# openmv.net
KiCad netlist of a schematic drawn in EAGLE
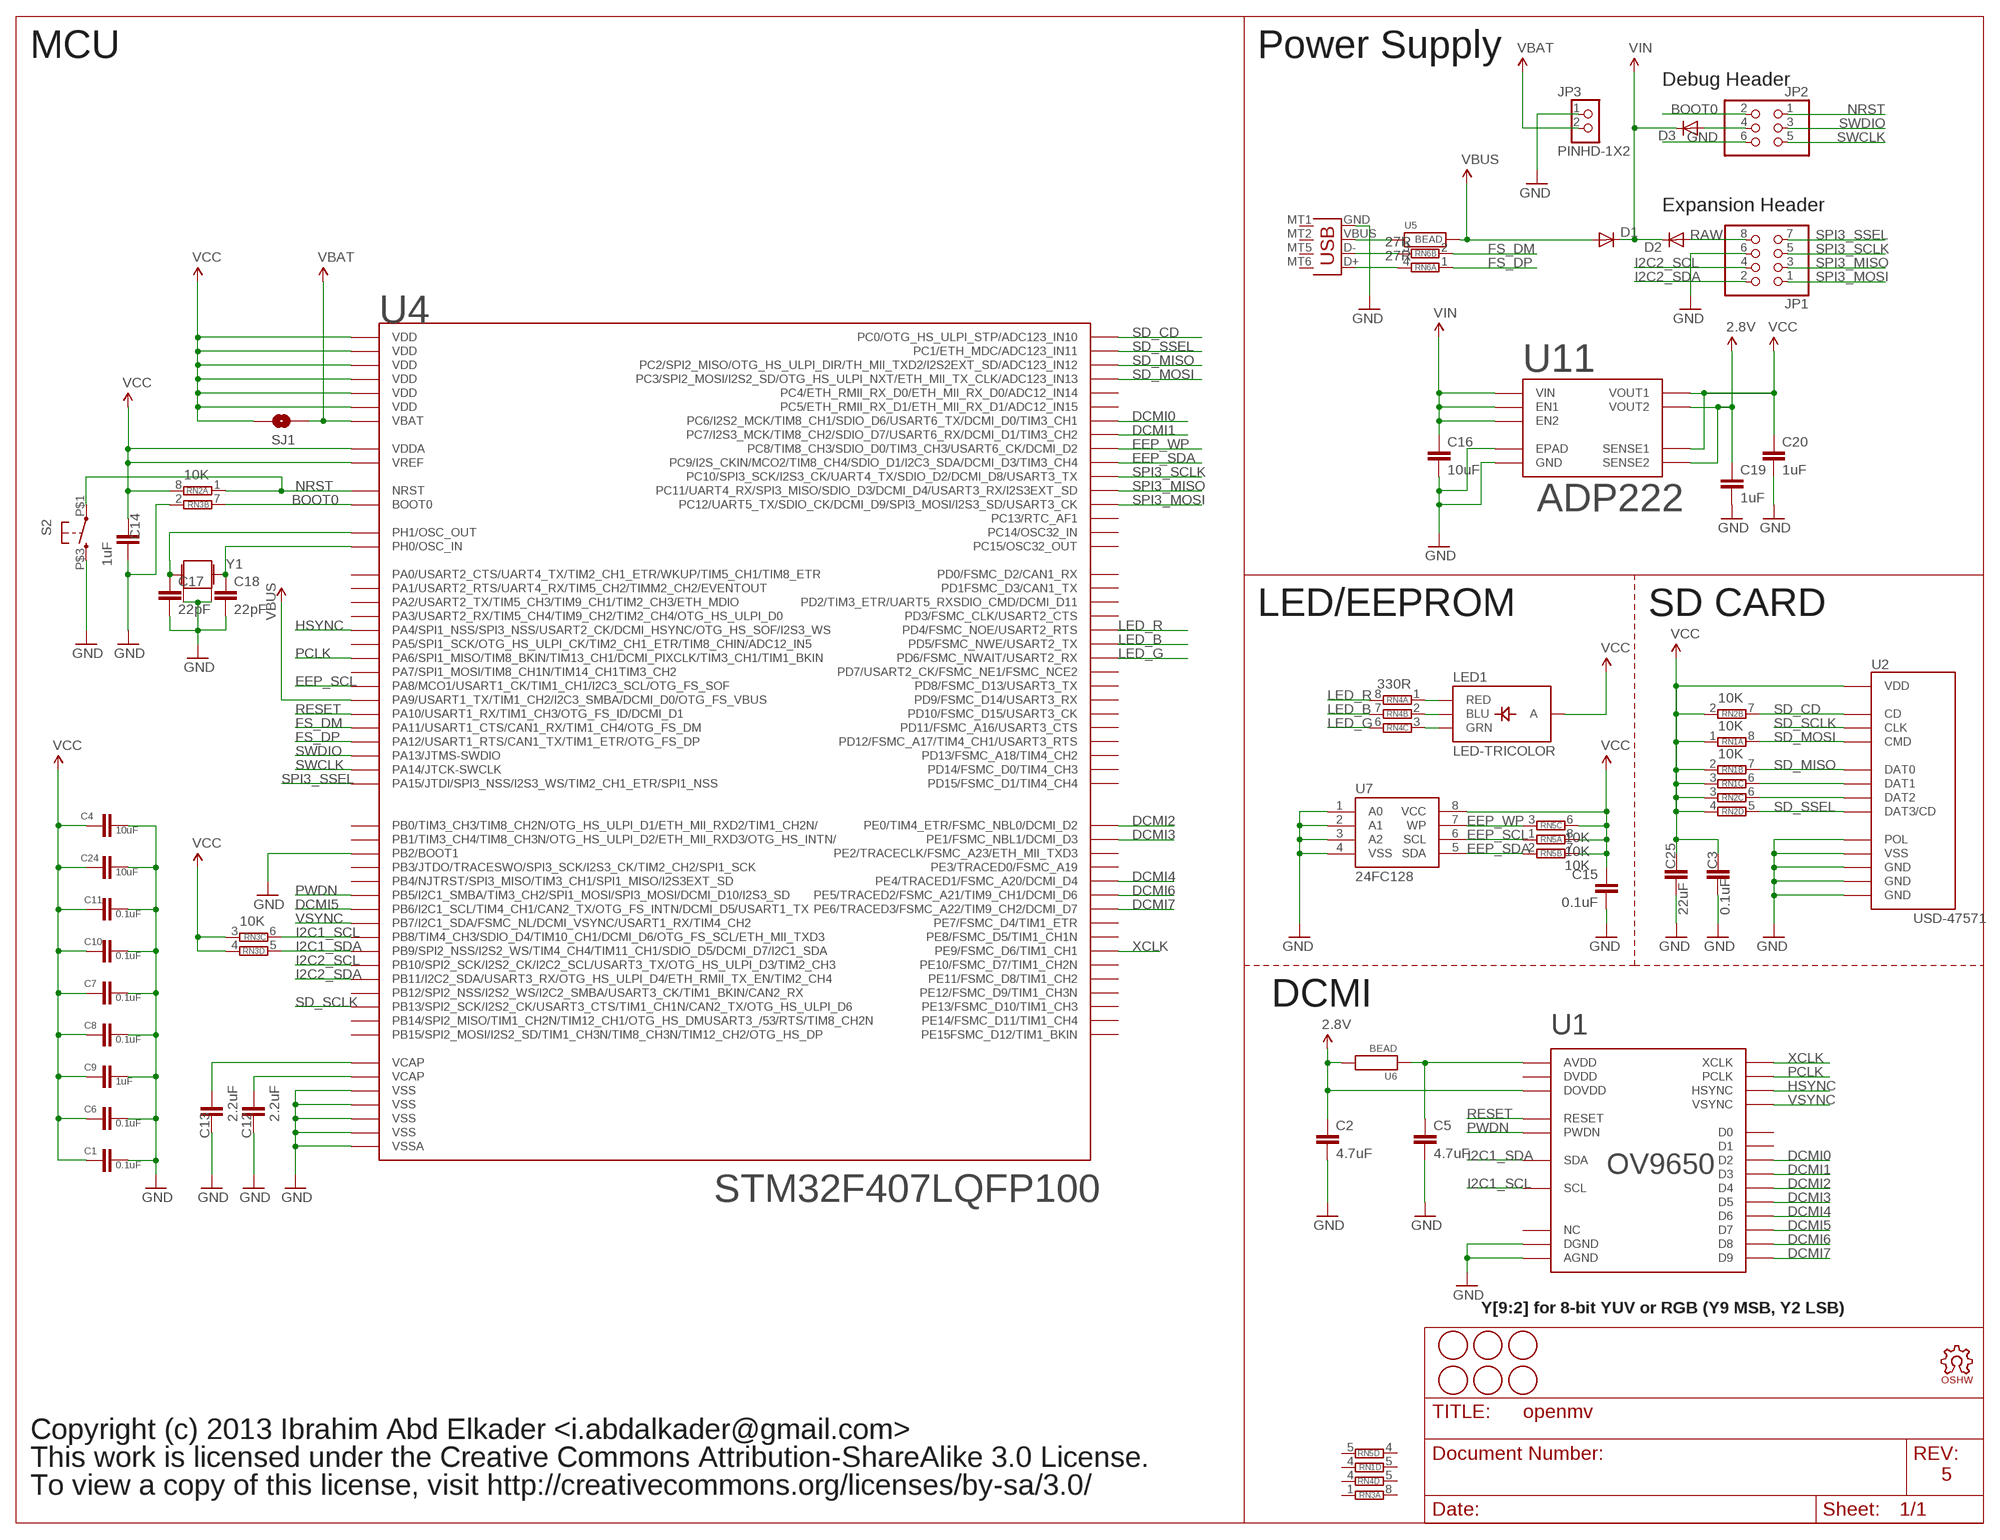
[diagram p0: schematic, sheet 1]

(export (version "E")
  (design (tool "Eeschema 10.0.6"))
  (components
    (comp (ref "C1")
      (value "0.1uF")
      (footprint "eagle-import:0402-CAP")
      (libsource (lib "eagle-import") (part "CAP0402-CAP"))
    )
    (comp (ref "C2")
      (value "4.7uF")
      (footprint "eagle-import:0402-CAP")
      (libsource (lib "eagle-import") (part "CAP0402-CAP"))
    )
    (comp (ref "C3")
      (value "0.1uF")
      (footprint "eagle-import:0402-CAP")
      (libsource (lib "eagle-import") (part "CAP0402-CAP"))
    )
    (comp (ref "C4")
      (value "10uF")
      (footprint "eagle-import:0805")
      (libsource (lib "eagle-import") (part "CAP0805"))
    )
    (comp (ref "C5")
      (value "4.7uF")
      (footprint "eagle-import:0402-CAP")
      (libsource (lib "eagle-import") (part "CAP0402-CAP"))
    )
    (comp (ref "C6")
      (value "0.1uF")
      (footprint "eagle-import:0402-CAP")
      (libsource (lib "eagle-import") (part "CAP0402-CAP"))
    )
    (comp (ref "C7")
      (value "0.1uF")
      (footprint "eagle-import:0402-CAP")
      (libsource (lib "eagle-import") (part "CAP0402-CAP"))
    )
    (comp (ref "C8")
      (value "0.1uF")
      (footprint "eagle-import:0402-CAP")
      (libsource (lib "eagle-import") (part "CAP0402-CAP"))
    )
    (comp (ref "C9")
      (value "1uF")
      (footprint "eagle-import:0402-CAP")
      (libsource (lib "eagle-import") (part "CAP0402-CAP"))
    )
    (comp (ref "C10")
      (value "0.1uF")
      (footprint "eagle-import:0402-CAP")
      (libsource (lib "eagle-import") (part "CAP0402-CAP"))
    )
    (comp (ref "C11")
      (value "0.1uF")
      (footprint "eagle-import:0402-CAP")
      (libsource (lib "eagle-import") (part "CAP0402-CAP"))
    )
    (comp (ref "C12")
      (value "2.2uF")
      (footprint "eagle-import:0402-CAP")
      (libsource (lib "eagle-import") (part "CAP0402-CAP"))
    )
    (comp (ref "C13")
      (value "2.2uF")
      (footprint "eagle-import:0402-CAP")
      (libsource (lib "eagle-import") (part "CAP0402-CAP"))
    )
    (comp (ref "C14")
      (value "1uF")
      (footprint "eagle-import:0402-CAP")
      (libsource (lib "eagle-import") (part "CAP0402-CAP"))
    )
    (comp (ref "C15")
      (value "0.1uF")
      (footprint "eagle-import:0402-CAP")
      (libsource (lib "eagle-import") (part "CAP0402-CAP"))
    )
    (comp (ref "C16")
      (value "10uF")
      (footprint "eagle-import:0805")
      (libsource (lib "eagle-import") (part "CAP0805"))
    )
    (comp (ref "C17")
      (value "22pF")
      (footprint "eagle-import:0402-CAP")
      (libsource (lib "eagle-import") (part "CAP0402-CAP"))
    )
    (comp (ref "C18")
      (value "22pF")
      (footprint "eagle-import:0402-CAP")
      (libsource (lib "eagle-import") (part "CAP0402-CAP"))
    )
    (comp (ref "C19")
      (value "1uF")
      (footprint "eagle-import:0402-CAP")
      (libsource (lib "eagle-import") (part "CAP0402-CAP"))
    )
    (comp (ref "C20")
      (value "1uF")
      (footprint "eagle-import:0402-CAP")
      (libsource (lib "eagle-import") (part "CAP0402-CAP"))
    )
    (comp (ref "C24")
      (value "10uF")
      (footprint "eagle-import:0805")
      (libsource (lib "eagle-import") (part "CAP0805"))
    )
    (comp (ref "C25")
      (value "22uF")
      (footprint "eagle-import:0805")
      (libsource (lib "eagle-import") (part "CAP0805"))
    )
    (comp (ref "D1")
      (value "DIODESOD")
      (footprint "eagle-import:SOD-323")
      (libsource (lib "eagle-import") (part "DIODESOD"))
    )
    (comp (ref "D2")
      (value "DIODESOD")
      (footprint "eagle-import:SOD-323")
      (libsource (lib "eagle-import") (part "DIODESOD"))
    )
    (comp (ref "D3")
      (value "DIODESOD")
      (footprint "eagle-import:SOD-323")
      (libsource (lib "eagle-import") (part "DIODESOD"))
    )
    (comp (ref "JP1")
      (value "PINHD-2X4")
      (footprint "eagle-import:2X04")
      (libsource (lib "eagle-import") (part "PINHD-2X4"))
    )
    (comp (ref "JP2")
      (value "PINHD-2X3")
      (footprint "eagle-import:2X03")
      (libsource (lib "eagle-import") (part "PINHD-2X3"))
    )
    (comp (ref "JP3")
      (value "PINHD-1X2")
      (footprint "eagle-import:1X2")
      (libsource (lib "eagle-import") (part "PINHD-1X2"))
    )
    (comp (ref "LED1")
      (value "LED-TRICOLOR")
      (footprint "eagle-import:LED-TRICOLOR-SMD")
      (libsource (lib "eagle-import") (part "LED-TRICOLOR"))
    )
    (comp (ref "LOGO1")
      (value "OSHW_LOGO_FILLX0150-NT")
      (footprint "eagle-import:OSHW_FILLX150_NOTEXT")
      (libsource (lib "eagle-import") (part "OSHW_LOGO_FILLX0150-NT"))
    )
    (comp (ref "RN1")
      (value "10K")
      (footprint "eagle-import:CAT16")
      (fields (field (name "OC_FARNELL") "unknown") (field (name "OC_NEWARK") "unknown"))
      (libsource (lib "eagle-import") (part "4R-NCAT16"))
    )
    (comp (ref "RN2")
      (value "10K")
      (footprint "eagle-import:CAT16")
      (fields (field (name "OC_FARNELL") "unknown") (field (name "OC_NEWARK") "unknown"))
      (libsource (lib "eagle-import") (part "4R-NCAT16"))
    )
    (comp (ref "RN3")
      (value "10K")
      (footprint "eagle-import:CAT16")
      (libsource (lib "eagle-import") (part "4R-NCAT16"))
    )
    (comp (ref "RN4")
      (value "330R")
      (footprint "eagle-import:CAT16")
      (fields (field (name "OC_FARNELL") "unknown") (field (name "OC_NEWARK") "unknown"))
      (libsource (lib "eagle-import") (part "4R-NCAT16"))
    )
    (comp (ref "RN5")
      (value "10K")
      (footprint "eagle-import:CAT16")
      (fields (field (name "OC_FARNELL") "unknown") (field (name "OC_NEWARK") "unknown"))
      (libsource (lib "eagle-import") (part "4R-NCAT16"))
    )
    (comp (ref "RN6")
      (value "27R")
      (footprint "eagle-import:EXBV4V")
      (libsource (lib "eagle-import") (part "2R-NEXBV4V"))
    )
    (comp (ref "S2")
      (value "SWITCHKMR442G")
      (footprint "eagle-import:KMR442G")
      (libsource (lib "eagle-import") (part "SWITCHKMR442G"))
    )
    (comp (ref "SJ1")
      (value "SOLDERJUMPERTRACE")
      (footprint "eagle-import:SJ_2S-TRACE")
      (libsource (lib "eagle-import") (part "SOLDERJUMPERTRACE"))
    )
    (comp (ref "U$3")
      (value "FIDUCIAL")
      (footprint "eagle-import:FIDUCIAL_1MM")
      (libsource (lib "eagle-import") (part "FIDUCIAL"))
    )
    (comp (ref "U$4")
      (value "FIDUCIAL")
      (footprint "eagle-import:FIDUCIAL_1MM")
      (libsource (lib "eagle-import") (part "FIDUCIAL"))
    )
    (comp (ref "U$5")
      (value "FIDUCIAL")
      (footprint "eagle-import:FIDUCIAL_1MM")
      (libsource (lib "eagle-import") (part "FIDUCIAL"))
    )
    (comp (ref "U$7")
      (value "FIDUCIAL")
      (footprint "eagle-import:FIDUCIAL_1MM")
      (libsource (lib "eagle-import") (part "FIDUCIAL"))
    )
    (comp (ref "U$9")
      (value "FIDUCIAL")
      (footprint "eagle-import:FIDUCIAL_1MM")
      (libsource (lib "eagle-import") (part "FIDUCIAL"))
    )
    (comp (ref "U$10")
      (value "FIDUCIAL")
      (footprint "eagle-import:FIDUCIAL_1MM")
      (libsource (lib "eagle-import") (part "FIDUCIAL"))
    )
    (comp (ref "U1")
      (value "OV9650")
      (footprint "eagle-import:OV9650")
      (libsource (lib "eagle-import") (part "OV9650"))
    )
    (comp (ref "U2")
      (value "USD-47571")
      (footprint "eagle-import:USD-47571")
      (libsource (lib "eagle-import") (part "USD-47571"))
    )
    (comp (ref "U4")
      (value "STM32F407LQFP100")
      (footprint "eagle-import:LQFP100")
      (libsource (lib "eagle-import") (part "STM32F407LQFP100"))
    )
    (comp (ref "U5")
      (value "BEAD")
      (footprint "eagle-import:0402-CAP")
      (libsource (lib "eagle-import") (part "BEAD"))
    )
    (comp (ref "U6")
      (value "BEAD")
      (footprint "eagle-import:0402-CAP")
      (libsource (lib "eagle-import") (part "BEAD"))
    )
    (comp (ref "U7")
      (value "24FC128")
      (footprint "eagle-import:MSOP8")
      (libsource (lib "eagle-import") (part "24FC128"))
    )
    (comp (ref "U11")
      (value "ADP222")
      (footprint "eagle-import:LFCSP8")
      (libsource (lib "eagle-import") (part "ADP222"))
    )
    (comp (ref "X1")
      (value "USB-MICROB")
      (footprint "eagle-import:USB-MICROB")
      (libsource (lib "eagle-import") (part "USB-MICROB"))
    )
    (comp (ref "Y1")
      (value "CRYSTAL2.5X2.0")
      (footprint "eagle-import:CRYSTAL-2.5X2.0")
      (libsource (lib "eagle-import") (part "CRYSTAL2.5X2.0"))
    )
  )
  (nets
    (net (code "1") (name "/BOOT0") (class "Default")
      (node (ref "JP2") (pin "2") (pinfunction "2_2") (pintype "passive"))
      (node (ref "RN3") (pin "7") (pinfunction "2_7") (pintype "passive"))
      (node (ref "U4") (pin "94") (pinfunction "BOOT0_94") (pintype "bidirectional"))
    )
    (net (code "2") (name "/DCMI0") (class "Default")
      (node (ref "U1") (pin "P$19") (pinfunction "D2_P$19") (pintype "bidirectional"))
      (node (ref "U4") (pin "63") (pinfunction "PC6/I2S2_MCK/TIM8_CH1/SDIO_D6/USART6_TX/DCMI_D0/TIM3_CH1_63") (pintype "bidirectional"))
    )
    (net (code "3") (name "/DCMI1") (class "Default")
      (node (ref "U1") (pin "P$21") (pinfunction "D3_P$21") (pintype "bidirectional"))
      (node (ref "U4") (pin "64") (pinfunction "PC7/I2S3_MCK/TIM8_CH2/SDIO_D7/USART6_RX/DCMI_D1/TIM3_CH2_64") (pintype "bidirectional"))
    )
    (net (code "4") (name "/DCMI2") (class "Default")
      (node (ref "U1") (pin "P$22") (pinfunction "D4_P$22") (pintype "bidirectional"))
      (node (ref "U4") (pin "97") (pinfunction "PE0/TIM4_ETR/FSMC_NBL0/DCMI_D2_97") (pintype "bidirectional"))
    )
    (net (code "5") (name "/DCMI3") (class "Default")
      (node (ref "U1") (pin "P$20") (pinfunction "D5_P$20") (pintype "bidirectional"))
      (node (ref "U4") (pin "98") (pinfunction "PE1/FSMC_NBL1/DCMI_D3_98") (pintype "bidirectional"))
    )
    (net (code "6") (name "/DCMI4") (class "Default")
      (node (ref "U1") (pin "P$18") (pinfunction "D6_P$18") (pintype "bidirectional"))
      (node (ref "U4") (pin "3") (pinfunction "PE4/TRACED1/FSMC_A20/DCMI_D4_3") (pintype "bidirectional"))
    )
    (net (code "7") (name "/DCMI5") (class "Default")
      (node (ref "U1") (pin "P$16") (pinfunction "D7_P$16") (pintype "bidirectional"))
      (node (ref "U4") (pin "92") (pinfunction "PB6/I2C1_SCL/TIM4_CH1/CAN2_TX/OTG_FS_INTN/DCMI_D5/USART1_TX_92") (pintype "bidirectional"))
    )
    (net (code "8") (name "/DCMI6") (class "Default")
      (node (ref "U1") (pin "P$14") (pinfunction "D8_P$14") (pintype "bidirectional"))
      (node (ref "U4") (pin "4") (pinfunction "PE5/TRACED2/FSMC_A21/TIM9_CH1/DCMI_D6_4") (pintype "bidirectional"))
    )
    (net (code "9") (name "/DCMI7") (class "Default")
      (node (ref "U1") (pin "P$12") (pinfunction "D9_P$12") (pintype "bidirectional"))
      (node (ref "U4") (pin "5") (pinfunction "PE6/TRACED3/FSMC_A22/TIM9_CH2/DCMI_D7_5") (pintype "bidirectional"))
    )
    (net (code "10") (name "/EEP_SCL") (class "Default")
      (node (ref "RN5") (pin "1") (pinfunction "1_1") (pintype "passive"))
      (node (ref "U4") (pin "67") (pinfunction "PA8/MCO1/USART1_CK/TIM1_CH1/I2C3_SCL/OTG_FS_SOF_67") (pintype "bidirectional"))
      (node (ref "U7") (pin "6") (pinfunction "SCL_6") (pintype "bidirectional"))
    )
    (net (code "11") (name "/EEP_SDA") (class "Default")
      (node (ref "RN5") (pin "2") (pinfunction "1_2") (pintype "passive"))
      (node (ref "U4") (pin "66") (pinfunction "PC9/I2S_CKIN/MCO2/TIM8_CH4/SDIO_D1/I2C3_SDA/DCMI_D3/TIM3_CH4_66") (pintype "bidirectional"))
      (node (ref "U7") (pin "5") (pinfunction "SDA_5") (pintype "bidirectional"))
    )
    (net (code "12") (name "/EEP_WP") (class "Default")
      (node (ref "RN5") (pin "3") (pinfunction "1_3") (pintype "passive"))
      (node (ref "U4") (pin "65") (pinfunction "PC8/TIM8_CH3/SDIO_D0/TIM3_CH3/USART6_CK/DCMI_D2_65") (pintype "bidirectional"))
      (node (ref "U7") (pin "7") (pinfunction "WP_7") (pintype "bidirectional"))
    )
    (net (code "13") (name "/FS_DM") (class "Default")
      (node (ref "RN6") (pin "2") (pinfunction "1_2") (pintype "passive"))
      (node (ref "U4") (pin "70") (pinfunction "PA11/USART1_CTS/CAN1_RX/TIM1_CH4/OTG_FS_DM_70") (pintype "bidirectional"))
    )
    (net (code "14") (name "/FS_DP") (class "Default")
      (node (ref "RN6") (pin "1") (pinfunction "1_1") (pintype "passive"))
      (node (ref "U4") (pin "71") (pinfunction "PA12/USART1_RTS/CAN1_TX/TIM1_ETR/OTG_FS_DP_71") (pintype "bidirectional"))
    )
    (net (code "15") (name "/HSYNC") (class "Default")
      (node (ref "U1") (pin "P$9") (pinfunction "HSYNC_P$9") (pintype "bidirectional"))
      (node (ref "U4") (pin "29") (pinfunction "PA4/SPI1_NSS/SPI3_NSS/USART2_CK/DCMI_HSYNC/OTG_HS_SOF/I2S3_WS_29") (pintype "bidirectional"))
    )
    (net (code "16") (name "/I2C1_SCL") (class "Default")
      (node (ref "RN3") (pin "6") (pinfunction "2_6") (pintype "passive"))
      (node (ref "U1") (pin "P$5") (pinfunction "SCL_P$5") (pintype "bidirectional"))
      (node (ref "U4") (pin "95") (pinfunction "PB8/TIM4_CH3/SDIO_D4/TIM10_CH1/DCMI_D6/OTG_FS_SCL/ETH_MII_TXD3_95") (pintype "bidirectional"))
    )
    (net (code "17") (name "/I2C1_SDA") (class "Default")
      (node (ref "RN3") (pin "5") (pinfunction "2_5") (pintype "passive"))
      (node (ref "U1") (pin "P$3") (pinfunction "SDA_P$3") (pintype "bidirectional"))
      (node (ref "U4") (pin "96") (pinfunction "PB9/SPI2_NSS/I2S2_WS/TIM4_CH4/TIM11_CH1/SDIO_D5/DCMI_D7/I2C1_SDA_96") (pintype "bidirectional"))
    )
    (net (code "18") (name "/I2C2_SCL") (class "Default")
      (node (ref "JP1") (pin "4") (pinfunction "4_4") (pintype "passive"))
      (node (ref "U4") (pin "47") (pinfunction "PB10/SPI2_SCK/I2S2_CK/I2C2_SCL/USART3_TX/OTG_HS_ULPI_D3/TIM2_CH3_47") (pintype "bidirectional"))
    )
    (net (code "19") (name "/I2C2_SDA") (class "Default")
      (node (ref "JP1") (pin "2") (pinfunction "2_2") (pintype "passive"))
      (node (ref "U4") (pin "48") (pinfunction "PB11/I2C2_SDA/USART3_RX/OTG_HS_ULPI_D4/ETH_RMII_TX_EN/TIM2_CH4_48") (pintype "bidirectional"))
    )
    (net (code "20") (name "/LED_B") (class "Default")
      (node (ref "RN4") (pin "7") (pinfunction "2_7") (pintype "passive"))
      (node (ref "U4") (pin "86") (pinfunction "PD5/FSMC_NWE/USART2_TX_86") (pintype "bidirectional"))
    )
    (net (code "21") (name "/LED_G") (class "Default")
      (node (ref "RN4") (pin "6") (pinfunction "2_6") (pintype "passive"))
      (node (ref "U4") (pin "87") (pinfunction "PD6/FSMC_NWAIT/USART2_RX_87") (pintype "bidirectional"))
    )
    (net (code "22") (name "/LED_R") (class "Default")
      (node (ref "RN4") (pin "8") (pinfunction "2_8") (pintype "passive"))
      (node (ref "U4") (pin "85") (pinfunction "PD4/FSMC_NOE/USART2_RTS_85") (pintype "bidirectional"))
    )
    (net (code "23") (name "/NRST") (class "Default")
      (node (ref "JP2") (pin "1") (pinfunction "1_1") (pintype "passive"))
      (node (ref "RN2") (pin "1") (pinfunction "1_1") (pintype "passive"))
      (node (ref "S2") (pin "P$1") (pinfunction "1_P$1") (pintype "passive"))
      (node (ref "U4") (pin "14") (pinfunction "NRST_14") (pintype "bidirectional"))
    )
    (net (code "24") (name "/PCLK") (class "Default")
      (node (ref "U1") (pin "P$17") (pinfunction "PCLK_P$17") (pintype "bidirectional"))
      (node (ref "U4") (pin "31") (pinfunction "PA6/SPI1_MISO/TIM8_BKIN/TIM13_CH1/DCMI_PIXCLK/TIM3_CH1/TIM1_BKIN_31") (pintype "bidirectional"))
    )
    (net (code "25") (name "/PWDN") (class "Default")
      (node (ref "U1") (pin "P$8") (pinfunction "PWDN_P$8") (pintype "bidirectional"))
      (node (ref "U4") (pin "91") (pinfunction "PB5/I2C1_SMBA/TIM3_CH2/SPI1_MOSI/SPI3_MOSI/DCMI_D10/I2S3_SD_91") (pintype "bidirectional"))
    )
    (net (code "26") (name "/RAW") (class "Default")
      (node (ref "D2") (pin "2") (pinfunction "A_2") (pintype "passive"))
      (node (ref "JP1") (pin "8") (pinfunction "8_8") (pintype "passive"))
    )
    (net (code "27") (name "/RESET") (class "Default")
      (node (ref "U1") (pin "P$6") (pinfunction "RESET_P$6") (pintype "bidirectional"))
      (node (ref "U4") (pin "69") (pinfunction "PA10/USART1_RX/TIM1_CH3/OTG_FS_ID/DCMI_D1_69") (pintype "bidirectional"))
    )
    (net (code "28") (name "/SD_CD") (class "Default")
      (node (ref "RN2") (pin "7") (pinfunction "2_7") (pintype "passive"))
      (node (ref "U2") (pin "G$5") (pinfunction "CD_G$5") (pintype "power_in"))
      (node (ref "U4") (pin "15") (pinfunction "PC0/OTG_HS_ULPI_STP/ADC123_IN10_15") (pintype "bidirectional"))
    )
    (net (code "29") (name "/SD_MISO") (class "Default")
      (node (ref "RN1") (pin "7") (pinfunction "2_7") (pintype "passive"))
      (node (ref "U2") (pin "P$7") (pinfunction "DAT0_P$7") (pintype "bidirectional"))
      (node (ref "U4") (pin "17") (pinfunction "PC2/SPI2_MISO/OTG_HS_ULPI_DIR/TH_MII_TXD2/I2S2EXT_SD/ADC123_IN12_17") (pintype "bidirectional"))
    )
    (net (code "30") (name "/SD_MOSI") (class "Default")
      (node (ref "RN1") (pin "8") (pinfunction "2_8") (pintype "passive"))
      (node (ref "U2") (pin "P$3") (pinfunction "CMD_P$3") (pintype "bidirectional"))
      (node (ref "U4") (pin "18") (pinfunction "PC3/SPI2_MOSI/I2S2_SD/OTG_HS_ULPI_NXT/ETH_MII_TX_CLK/ADC123_IN13_18") (pintype "bidirectional"))
    )
    (net (code "31") (name "/SD_SCLK") (class "Default")
      (node (ref "U2") (pin "P$5") (pinfunction "CLK_P$5") (pintype "bidirectional"))
      (node (ref "U4") (pin "52") (pinfunction "PB13/SPI2_SCK/I2S2_CK/USART3_CTS/TIM1_CH1N/CAN2_TX/OTG_HS_ULPI_D6_52") (pintype "bidirectional"))
    )
    (net (code "32") (name "/SD_SSEL") (class "Default")
      (node (ref "RN2") (pin "5") (pinfunction "2_5") (pintype "passive"))
      (node (ref "U2") (pin "P$2") (pinfunction "DAT3/CD_P$2") (pintype "bidirectional"))
      (node (ref "U4") (pin "16") (pinfunction "PC1/ETH_MDC/ADC123_IN11_16") (pintype "bidirectional"))
    )
    (net (code "33") (name "/SPI3_MISO") (class "Default")
      (node (ref "JP1") (pin "3") (pinfunction "3_3") (pintype "passive"))
      (node (ref "U4") (pin "79") (pinfunction "PC11/UART4_RX/SPI3_MISO/SDIO_D3/DCMI_D4/USART3_RX/I2S3EXT_SD_79") (pintype "bidirectional"))
    )
    (net (code "34") (name "/SPI3_MOSI") (class "Default")
      (node (ref "JP1") (pin "1") (pinfunction "1_1") (pintype "passive"))
      (node (ref "U4") (pin "80") (pinfunction "PC12/UART5_TX/SDIO_CK/DCMI_D9/SPI3_MOSI/I2S3_SD/USART3_CK_80") (pintype "bidirectional"))
    )
    (net (code "35") (name "/SPI3_SCLK") (class "Default")
      (node (ref "JP1") (pin "5") (pinfunction "5_5") (pintype "passive"))
      (node (ref "U4") (pin "78") (pinfunction "PC10/SPI3_SCK/I2S3_CK/UART4_TX/SDIO_D2/DCMI_D8/USART3_TX_78") (pintype "bidirectional"))
    )
    (net (code "36") (name "/SPI3_SSEL") (class "Default")
      (node (ref "JP1") (pin "7") (pinfunction "7_7") (pintype "passive"))
      (node (ref "U4") (pin "77") (pinfunction "PA15/JTDI/SPI3_NSS/I2S3_WS/TIM2_CH1_ETR/SPI1_NSS_77") (pintype "bidirectional"))
    )
    (net (code "37") (name "/SWCLK") (class "Default")
      (node (ref "JP2") (pin "5") (pinfunction "5_5") (pintype "passive"))
      (node (ref "U4") (pin "76") (pinfunction "PA14/JTCK-SWCLK_76") (pintype "bidirectional"))
    )
    (net (code "38") (name "/SWDIO") (class "Default")
      (node (ref "JP2") (pin "3") (pinfunction "3_3") (pintype "passive"))
      (node (ref "U4") (pin "72") (pinfunction "PA13/JTMS-SWDIO_72") (pintype "bidirectional"))
    )
    (net (code "39") (name "/VSYNC") (class "Default")
      (node (ref "U1") (pin "P$7") (pinfunction "VSYNC_P$7") (pintype "bidirectional"))
      (node (ref "U4") (pin "93") (pinfunction "PB7/I2C1_SDA/FSMC_NL/DCMI_VSYNC/USART1_RX/TIM4_CH2_93") (pintype "bidirectional"))
    )
    (net (code "40") (name "/XCLK") (class "Default")
      (node (ref "U1") (pin "P$13") (pinfunction "XCLK_P$13") (pintype "bidirectional"))
      (node (ref "U4") (pin "40") (pinfunction "PE9/FSMC_D6/TIM1_CH1_40") (pintype "bidirectional"))
    )
    (net (code "41") (name "2.8V") (class "Default")
      (node (ref "C19") (pin "1") (pinfunction "1_1") (pintype "passive"))
      (node (ref "C2") (pin "1") (pinfunction "1_1") (pintype "passive"))
      (node (ref "U1") (pin "P$11") (pinfunction "DOVDD_P$11") (pintype "bidirectional"))
      (node (ref "U11") (pin "4") (pinfunction "SENSE2_4") (pintype "passive"))
      (node (ref "U11") (pin "5") (pinfunction "VOUT2_5") (pintype "passive"))
      (node (ref "U6") (pin "2") (pinfunction "2_2") (pintype "passive"))
    )
    (net (code "42") (name "GND") (class "Default")
      (node (ref "C1") (pin "1") (pinfunction "1_1") (pintype "passive"))
      (node (ref "C10") (pin "2") (pinfunction "2_2") (pintype "passive"))
      (node (ref "C11") (pin "2") (pinfunction "2_2") (pintype "passive"))
      (node (ref "C12") (pin "2") (pinfunction "2_2") (pintype "passive"))
      (node (ref "C13") (pin "2") (pinfunction "2_2") (pintype "passive"))
      (node (ref "C14") (pin "1") (pinfunction "1_1") (pintype "passive"))
      (node (ref "C15") (pin "2") (pinfunction "2_2") (pintype "passive"))
      (node (ref "C16") (pin "2") (pinfunction "2_2") (pintype "passive"))
      (node (ref "C17") (pin "2") (pinfunction "2_2") (pintype "passive"))
      (node (ref "C18") (pin "2") (pinfunction "2_2") (pintype "passive"))
      (node (ref "C19") (pin "2") (pinfunction "2_2") (pintype "passive"))
      (node (ref "C2") (pin "2") (pinfunction "2_2") (pintype "passive"))
      (node (ref "C20") (pin "2") (pinfunction "2_2") (pintype "passive"))
      (node (ref "C24") (pin "1") (pinfunction "1_1") (pintype "passive"))
      (node (ref "C25") (pin "2") (pinfunction "2_2") (pintype "passive"))
      (node (ref "C3") (pin "2") (pinfunction "2_2") (pintype "passive"))
      (node (ref "C4") (pin "1") (pinfunction "1_1") (pintype "passive"))
      (node (ref "C5") (pin "2") (pinfunction "2_2") (pintype "passive"))
      (node (ref "C6") (pin "1") (pinfunction "1_1") (pintype "passive"))
      (node (ref "C7") (pin "2") (pinfunction "2_2") (pintype "passive"))
      (node (ref "C8") (pin "1") (pinfunction "1_1") (pintype "passive"))
      (node (ref "C9") (pin "1") (pinfunction "1_1") (pintype "passive"))
      (node (ref "JP1") (pin "6") (pinfunction "6_6") (pintype "passive"))
      (node (ref "JP2") (pin "6") (pinfunction "6_6") (pintype "passive"))
      (node (ref "JP3") (pin "1") (pinfunction "1_1") (pintype "passive"))
      (node (ref "RN3") (pin "2") (pinfunction "1_2") (pintype "passive"))
      (node (ref "S2") (pin "P$3") (pinfunction "2_P$3") (pintype "passive"))
      (node (ref "U1") (pin "P$15") (pinfunction "DGND_P$15") (pintype "bidirectional"))
      (node (ref "U1") (pin "P$2") (pinfunction "AGND_P$2") (pintype "power_in"))
      (node (ref "U11") (pin "3") (pinfunction "GND_3") (pintype "power_in"))
      (node (ref "U11") (pin "EXP") (pinfunction "EPAD_EXP") (pintype "input"))
      (node (ref "U2") (pin "G$1") (pinfunction "GND_G$1") (pintype "power_in"))
      (node (ref "U2") (pin "G$2") (pinfunction "GND_G$2") (pintype "power_in"))
      (node (ref "U2") (pin "G$3") (pinfunction "GND_G$3") (pintype "power_in"))
      (node (ref "U2") (pin "G$4") (pinfunction "POL_G$4") (pintype "power_in"))
      (node (ref "U2") (pin "P$6") (pinfunction "VSS_P$6") (pintype "power_in"))
      (node (ref "U4") (pin "10") (pinfunction "VSS_10") (pintype "power_in"))
      (node (ref "U4") (pin "20") (pinfunction "VSSA_20") (pintype "power_in"))
      (node (ref "U4") (pin "27") (pinfunction "VSS_27") (pintype "power_in"))
      (node (ref "U4") (pin "37") (pinfunction "PB2/BOOT1_37") (pintype "bidirectional"))
      (node (ref "U4") (pin "74") (pinfunction "VSS_74") (pintype "power_in"))
      (node (ref "U4") (pin "99") (pinfunction "VSS_99") (pintype "power_in"))
      (node (ref "U7") (pin "1") (pinfunction "A0_1") (pintype "bidirectional"))
      (node (ref "U7") (pin "2") (pinfunction "A1_2") (pintype "bidirectional"))
      (node (ref "U7") (pin "3") (pinfunction "A2_3") (pintype "bidirectional"))
      (node (ref "U7") (pin "4") (pinfunction "VSS_4") (pintype "power_in"))
      (node (ref "X1") (pin "GND") (pinfunction "GND_GND") (pintype "bidirectional"))
      (node (ref "Y1") (pin "2") (pinfunction "P$1_2") (pintype "power_in"))
      (node (ref "Y1") (pin "4") (pinfunction "P$2_4") (pintype "power_in"))
    )
    (net (code "43") (name "Net-(C12-Pad1)") (class "Default")
      (node (ref "C12") (pin "1") (pinfunction "1_1") (pintype "passive"))
      (node (ref "U4") (pin "73") (pinfunction "VCAP_73") (pintype "power_in"))
    )
    (net (code "44") (name "Net-(C13-Pad1)") (class "Default")
      (node (ref "C13") (pin "1") (pinfunction "1_1") (pintype "passive"))
      (node (ref "U4") (pin "49") (pinfunction "VCAP_49") (pintype "power_in"))
    )
    (net (code "45") (name "Net-(D3-A)") (class "Default")
      (node (ref "D3") (pin "2") (pinfunction "A_2") (pintype "passive"))
      (node (ref "JP2") (pin "4") (pinfunction "4_4") (pintype "passive"))
    )
    (net (code "46") (name "Net-(LED1-BLU)") (class "Default")
      (node (ref "LED1") (pin "B") (pinfunction "BLU_B") (pintype "bidirectional"))
      (node (ref "RN4") (pin "2") (pinfunction "1_2") (pintype "passive"))
    )
    (net (code "47") (name "Net-(LED1-GRN)") (class "Default")
      (node (ref "LED1") (pin "G") (pinfunction "GRN_G") (pintype "bidirectional"))
      (node (ref "RN4") (pin "3") (pinfunction "1_3") (pintype "passive"))
    )
    (net (code "48") (name "Net-(LED1-RED)") (class "Default")
      (node (ref "LED1") (pin "R") (pinfunction "RED_R") (pintype "bidirectional"))
      (node (ref "RN4") (pin "1") (pinfunction "1_1") (pintype "passive"))
    )
    (net (code "49") (name "Net-(RN1C-2)") (class "Default")
      (node (ref "RN1") (pin "6") (pinfunction "2_6") (pintype "passive"))
      (node (ref "U2") (pin "P$8") (pinfunction "DAT1_P$8") (pintype "bidirectional"))
    )
    (net (code "50") (name "Net-(RN2C-2)") (class "Default")
      (node (ref "RN2") (pin "6") (pinfunction "2_6") (pintype "passive"))
      (node (ref "U2") (pin "P$1") (pinfunction "DAT2_P$1") (pintype "bidirectional"))
    )
    (net (code "51") (name "Net-(RN6A-2)") (class "Default")
      (node (ref "RN6") (pin "4") (pinfunction "2_4") (pintype "passive"))
      (node (ref "X1") (pin "D+") (pinfunction "D+_D+") (pintype "bidirectional"))
    )
    (net (code "52") (name "Net-(RN6B-2)") (class "Default")
      (node (ref "RN6") (pin "3") (pinfunction "2_3") (pintype "passive"))
      (node (ref "X1") (pin "D-") (pinfunction "D-_D-") (pintype "bidirectional"))
    )
    (net (code "53") (name "Net-(U1-AVDD)") (class "Default")
      (node (ref "C5") (pin "1") (pinfunction "1_1") (pintype "passive"))
      (node (ref "U1") (pin "P$4") (pinfunction "AVDD_P$4") (pintype "power_in"))
      (node (ref "U6") (pin "1") (pinfunction "1_1") (pintype "passive"))
    )
    (net (code "54") (name "Net-(U4-PH0{slash}OSC_IN)") (class "Default")
      (node (ref "C18") (pin "1") (pinfunction "1_1") (pintype "passive"))
      (node (ref "U4") (pin "12") (pinfunction "PH0/OSC_IN_12") (pintype "bidirectional"))
      (node (ref "Y1") (pin "1") (pinfunction "1_1") (pintype "passive"))
    )
    (net (code "55") (name "Net-(U4-PH1{slash}OSC_OUT)") (class "Default")
      (node (ref "C17") (pin "1") (pinfunction "1_1") (pintype "passive"))
      (node (ref "U4") (pin "13") (pinfunction "PH1/OSC_OUT_13") (pintype "bidirectional"))
      (node (ref "Y1") (pin "3") (pinfunction "2_3") (pintype "passive"))
    )
    (net (code "56") (name "Net-(U5-Pad1)") (class "Default")
      (node (ref "U5") (pin "1") (pinfunction "1_1") (pintype "passive"))
      (node (ref "X1") (pin "VBUS") (pinfunction "VBUS_VBUS") (pintype "bidirectional"))
    )
    (net (code "57") (name "VBAT") (class "Default")
      (node (ref "JP3") (pin "2") (pinfunction "2_2") (pintype "passive"))
      (node (ref "SJ1") (pin "1") (pinfunction "1_1") (pintype "passive"))
      (node (ref "U4") (pin "6") (pinfunction "VBAT_6") (pintype "power_in"))
    )
    (net (code "58") (name "VBUS") (class "Default")
      (node (ref "D1") (pin "2") (pinfunction "A_2") (pintype "passive"))
      (node (ref "U4") (pin "68") (pinfunction "PA9/USART1_TX/TIM1_CH2/I2C3_SMBA/DCMI_D0/OTG_FS_VBUS_68") (pintype "bidirectional"))
      (node (ref "U5") (pin "2") (pinfunction "2_2") (pintype "passive"))
    )
    (net (code "59") (name "VCC") (class "Default")
      (node (ref "C1") (pin "2") (pinfunction "2_2") (pintype "passive"))
      (node (ref "C10") (pin "1") (pinfunction "1_1") (pintype "passive"))
      (node (ref "C11") (pin "1") (pinfunction "1_1") (pintype "passive"))
      (node (ref "C14") (pin "2") (pinfunction "2_2") (pintype "passive"))
      (node (ref "C15") (pin "1") (pinfunction "1_1") (pintype "passive"))
      (node (ref "C20") (pin "1") (pinfunction "1_1") (pintype "passive"))
      (node (ref "C24") (pin "2") (pinfunction "2_2") (pintype "passive"))
      (node (ref "C25") (pin "1") (pinfunction "1_1") (pintype "passive"))
      (node (ref "C3") (pin "1") (pinfunction "1_1") (pintype "passive"))
      (node (ref "C4") (pin "2") (pinfunction "2_2") (pintype "passive"))
      (node (ref "C6") (pin "2") (pinfunction "2_2") (pintype "passive"))
      (node (ref "C7") (pin "1") (pinfunction "1_1") (pintype "passive"))
      (node (ref "C8") (pin "2") (pinfunction "2_2") (pintype "passive"))
      (node (ref "C9") (pin "2") (pinfunction "2_2") (pintype "passive"))
      (node (ref "LED1") (pin "A") (pinfunction "A_A") (pintype "bidirectional"))
      (node (ref "RN1") (pin "1") (pinfunction "1_1") (pintype "passive"))
      (node (ref "RN1") (pin "2") (pinfunction "1_2") (pintype "passive"))
      (node (ref "RN1") (pin "3") (pinfunction "1_3") (pintype "passive"))
      (node (ref "RN2") (pin "2") (pinfunction "1_2") (pintype "passive"))
      (node (ref "RN2") (pin "3") (pinfunction "1_3") (pintype "passive"))
      (node (ref "RN2") (pin "4") (pinfunction "1_4") (pintype "passive"))
      (node (ref "RN2") (pin "8") (pinfunction "2_8") (pintype "passive"))
      (node (ref "RN3") (pin "3") (pinfunction "1_3") (pintype "passive"))
      (node (ref "RN3") (pin "4") (pinfunction "1_4") (pintype "passive"))
      (node (ref "RN5") (pin "6") (pinfunction "2_6") (pintype "passive"))
      (node (ref "RN5") (pin "7") (pinfunction "2_7") (pintype "passive"))
      (node (ref "RN5") (pin "8") (pinfunction "2_8") (pintype "passive"))
      (node (ref "SJ1") (pin "2") (pinfunction "2_2") (pintype "passive"))
      (node (ref "U11") (pin "7") (pinfunction "VOUT1_7") (pintype "passive"))
      (node (ref "U11") (pin "8") (pinfunction "SENSE1_8") (pintype "passive"))
      (node (ref "U2") (pin "P$4") (pinfunction "VDD_P$4") (pintype "power_in"))
      (node (ref "U4") (pin "100") (pinfunction "VDD_100") (pintype "power_in"))
      (node (ref "U4") (pin "11") (pinfunction "VDD_11") (pintype "power_in"))
      (node (ref "U4") (pin "19") (pinfunction "VDD_19") (pintype "power_in"))
      (node (ref "U4") (pin "21") (pinfunction "VREF_21") (pintype "power_in"))
      (node (ref "U4") (pin "22") (pinfunction "VDDA_22") (pintype "power_in"))
      (node (ref "U4") (pin "28") (pinfunction "VDD_28") (pintype "power_in"))
      (node (ref "U4") (pin "50") (pinfunction "VDD_50") (pintype "power_in"))
      (node (ref "U4") (pin "75") (pinfunction "VDD_75") (pintype "power_in"))
      (node (ref "U7") (pin "8") (pinfunction "VCC_8") (pintype "power_in"))
    )
    (net (code "60") (name "VIN") (class "Default")
      (node (ref "C16") (pin "1") (pinfunction "1_1") (pintype "passive"))
      (node (ref "D1") (pin "1") (pinfunction "C_1") (pintype "passive"))
      (node (ref "D2") (pin "1") (pinfunction "C_1") (pintype "passive"))
      (node (ref "D3") (pin "1") (pinfunction "C_1") (pintype "passive"))
      (node (ref "U11") (pin "1") (pinfunction "EN1_1") (pintype "input"))
      (node (ref "U11") (pin "2") (pinfunction "EN2_2") (pintype "input"))
      (node (ref "U11") (pin "6") (pinfunction "VIN_6") (pintype "power_in"))
    )
    (net (code "61") (name "unconnected-(RN1D-1-Pad4)") (class "Default")
      (node (ref "RN1") (pin "4") (pinfunction "1_4") (pintype "passive"))
    )
    (net (code "62") (name "unconnected-(RN1D-2-Pad5)") (class "Default")
      (node (ref "RN1") (pin "5") (pinfunction "2_5") (pintype "passive"))
    )
    (net (code "63") (name "unconnected-(RN3-Pad1)") (class "Default")
      (node (ref "RN3") (pin "1") (pinfunction "1_1") (pintype "passive"))
    )
    (net (code "64") (name "unconnected-(RN3A-2-Pad8)") (class "Default")
      (node (ref "RN3") (pin "8") (pinfunction "2_8") (pintype "passive"))
    )
    (net (code "65") (name "unconnected-(RN4D-1-Pad4)") (class "Default")
      (node (ref "RN4") (pin "4") (pinfunction "1_4") (pintype "passive"))
    )
    (net (code "66") (name "unconnected-(RN4D-2-Pad5)") (class "Default")
      (node (ref "RN4") (pin "5") (pinfunction "2_5") (pintype "passive"))
    )
    (net (code "67") (name "unconnected-(RN5D-1-Pad4)") (class "Default")
      (node (ref "RN5") (pin "4") (pinfunction "1_4") (pintype "passive"))
    )
    (net (code "68") (name "unconnected-(RN5D-2-Pad5)") (class "Default")
      (node (ref "RN5") (pin "5") (pinfunction "2_5") (pintype "passive"))
    )
    (net (code "69") (name "unconnected-(U1-D0-PadP$24)") (class "Default")
      (node (ref "U1") (pin "P$24") (pinfunction "D0_P$24") (pintype "bidirectional"))
    )
    (net (code "70") (name "unconnected-(U1-D1-PadP$23)") (class "Default")
      (node (ref "U1") (pin "P$23") (pinfunction "D1_P$23") (pintype "bidirectional"))
    )
    (net (code "71") (name "unconnected-(U1-DVDD-PadP$10)") (class "Default")
      (node (ref "U1") (pin "P$10") (pinfunction "DVDD_P$10") (pintype "bidirectional"))
    )
    (net (code "72") (name "unconnected-(U1-NC-PadP$1)") (class "Default")
      (node (ref "U1") (pin "P$1") (pinfunction "NC_P$1") (pintype "no_connect"))
    )
    (net (code "73") (name "unconnected-(U4-PA0{slash}USART2_CTS{slash}UART4_TX{slash}TIM2_CH1_ETR{slash}WKUP{slash}TIM5_CH1{slash}TIM8_ETR-Pad23)") (class "Default")
      (node (ref "U4") (pin "23") (pinfunction "PA0/USART2_CTS/UART4_TX/TIM2_CH1_ETR/WKUP/TIM5_CH1/TIM8_ETR_23") (pintype "bidirectional"))
    )
    (net (code "74") (name "unconnected-(U4-PA1{slash}USART2_RTS{slash}UART4_RX{slash}TIM5_CH2{slash}TIMM2_CH2{slash}EVENTOUT-Pad24)") (class "Default")
      (node (ref "U4") (pin "24") (pinfunction "PA1/USART2_RTS/UART4_RX/TIM5_CH2/TIMM2_CH2/EVENTOUT_24") (pintype "bidirectional"))
    )
    (net (code "75") (name "unconnected-(U4-PA2{slash}USART2_TX{slash}TIM5_CH3{slash}TIM9_CH1{slash}TIM2_CH3{slash}ETH_MDIO-Pad25)") (class "Default")
      (node (ref "U4") (pin "25") (pinfunction "PA2/USART2_TX/TIM5_CH3/TIM9_CH1/TIM2_CH3/ETH_MDIO_25") (pintype "bidirectional"))
    )
    (net (code "76") (name "unconnected-(U4-PA3{slash}USART2_RX{slash}TIM5_CH4{slash}TIM9_CH2{slash}TIM2_CH4{slash}OTG_HS_ULPI_D0-Pad26)") (class "Default")
      (node (ref "U4") (pin "26") (pinfunction "PA3/USART2_RX/TIM5_CH4/TIM9_CH2/TIM2_CH4/OTG_HS_ULPI_D0_26") (pintype "bidirectional"))
    )
    (net (code "77") (name "unconnected-(U4-PA5{slash}SPI1_SCK{slash}OTG_HS_ULPI_CK{slash}TIM2_CH1_ETR{slash}TIM8_CHIN{slash}ADC12_IN5-Pad30)") (class "Default")
      (node (ref "U4") (pin "30") (pinfunction "PA5/SPI1_SCK/OTG_HS_ULPI_CK/TIM2_CH1_ETR/TIM8_CHIN/ADC12_IN5_30") (pintype "bidirectional"))
    )
    (net (code "78") (name "unconnected-(U4-PA7{slash}SPI1_MOSI{slash}TIM8_CH1N{slash}TIM14_CH1TIM3_CH2-Pad32)") (class "Default")
      (node (ref "U4") (pin "32") (pinfunction "PA7/SPI1_MOSI/TIM8_CH1N/TIM14_CH1TIM3_CH2_32") (pintype "bidirectional"))
    )
    (net (code "79") (name "unconnected-(U4-PB0{slash}TIM3_CH3{slash}TIM8_CH2N{slash}OTG_HS_ULPI_D1{slash}ETH_MII_RXD2{slash}TIM1_CH2N{slash}-Pad35)") (class "Default")
      (node (ref "U4") (pin "35") (pinfunction "PB0/TIM3_CH3/TIM8_CH2N/OTG_HS_ULPI_D1/ETH_MII_RXD2/TIM1_CH2N/_35") (pintype "bidirectional"))
    )
    (net (code "80") (name "unconnected-(U4-PB1{slash}TIM3_CH4{slash}TIM8_CH3N{slash}OTG_HS_ULPI_D2{slash}ETH_MII_RXD3{slash}OTG_HS_INTN{slash}-Pad36)") (class "Default")
      (node (ref "U4") (pin "36") (pinfunction "PB1/TIM3_CH4/TIM8_CH3N/OTG_HS_ULPI_D2/ETH_MII_RXD3/OTG_HS_INTN/_36") (pintype "bidirectional"))
    )
    (net (code "81") (name "unconnected-(U4-PB3{slash}JTDO{slash}TRACESWO{slash}SPI3_SCK{slash}I2S3_CK{slash}TIM2_CH2{slash}SPI1_SCK-Pad89)") (class "Default")
      (node (ref "U4") (pin "89") (pinfunction "PB3/JTDO/TRACESWO/SPI3_SCK/I2S3_CK/TIM2_CH2/SPI1_SCK_89") (pintype "bidirectional"))
    )
    (net (code "82") (name "unconnected-(U4-PB4{slash}NJTRST{slash}SPI3_MISO{slash}TIM3_CH1{slash}SPI1_MISO{slash}I2S3EXT_SD-Pad90)") (class "Default")
      (node (ref "U4") (pin "90") (pinfunction "PB4/NJTRST/SPI3_MISO/TIM3_CH1/SPI1_MISO/I2S3EXT_SD_90") (pintype "bidirectional"))
    )
    (net (code "83") (name "unconnected-(U4-PB12{slash}SPI2_NSS{slash}I2S2_WS{slash}I2C2_SMBA{slash}USART3_CK{slash}TIM1_BKIN{slash}CAN2_RX-Pad51)") (class "Default")
      (node (ref "U4") (pin "51") (pinfunction "PB12/SPI2_NSS/I2S2_WS/I2C2_SMBA/USART3_CK/TIM1_BKIN/CAN2_RX_51") (pintype "bidirectional"))
    )
    (net (code "84") (name "unconnected-(U4-PB14{slash}SPI2_MISO{slash}TIM1_CH2N{slash}TIM12_CH1{slash}OTG_HS_DMUSART3_{slash}53{slash}RTS{slash}TIM8_CH2N-Pad53)") (class "Default")
      (node (ref "U4") (pin "53") (pinfunction "PB14/SPI2_MISO/TIM1_CH2N/TIM12_CH1/OTG_HS_DMUSART3_/53/RTS/TIM8_CH2N_53") (pintype "bidirectional"))
    )
    (net (code "85") (name "unconnected-(U4-PB15{slash}SPI2_MOSI{slash}I2S2_SD{slash}TIM1_CH3N{slash}TIM8_CH3N{slash}TIM12_CH2{slash}OTG_HS_DP-Pad54)") (class "Default")
      (node (ref "U4") (pin "54") (pinfunction "PB15/SPI2_MOSI/I2S2_SD/TIM1_CH3N/TIM8_CH3N/TIM12_CH2/OTG_HS_DP_54") (pintype "bidirectional"))
    )
    (net (code "86") (name "unconnected-(U4-PC4{slash}ETH_RMII_RX_D0{slash}ETH_MII_RX_D0{slash}ADC12_IN14-Pad33)") (class "Default")
      (node (ref "U4") (pin "33") (pinfunction "PC4/ETH_RMII_RX_D0/ETH_MII_RX_D0/ADC12_IN14_33") (pintype "bidirectional"))
    )
    (net (code "87") (name "unconnected-(U4-PC5{slash}ETH_RMII_RX_D1{slash}ETH_MII_RX_D1{slash}ADC12_IN15-Pad34)") (class "Default")
      (node (ref "U4") (pin "34") (pinfunction "PC5/ETH_RMII_RX_D1/ETH_MII_RX_D1/ADC12_IN15_34") (pintype "bidirectional"))
    )
    (net (code "88") (name "unconnected-(U4-PC13{slash}RTC_AF1-Pad7)") (class "Default")
      (node (ref "U4") (pin "7") (pinfunction "PC13/RTC_AF1_7") (pintype "bidirectional"))
    )
    (net (code "89") (name "unconnected-(U4-PC14{slash}OSC32_IN-Pad8)") (class "Default")
      (node (ref "U4") (pin "8") (pinfunction "PC14/OSC32_IN_8") (pintype "bidirectional"))
    )
    (net (code "90") (name "unconnected-(U4-PC15{slash}OSC32_OUT-Pad9)") (class "Default")
      (node (ref "U4") (pin "9") (pinfunction "PC15/OSC32_OUT_9") (pintype "bidirectional"))
    )
    (net (code "91") (name "unconnected-(U4-PD0{slash}FSMC_D2{slash}CAN1_RX-Pad81)") (class "Default")
      (node (ref "U4") (pin "81") (pinfunction "PD0/FSMC_D2/CAN1_RX_81") (pintype "bidirectional"))
    )
    (net (code "92") (name "unconnected-(U4-PD1FSMC_D3{slash}CAN1_TX-Pad82)") (class "Default")
      (node (ref "U4") (pin "82") (pinfunction "PD1FSMC_D3/CAN1_TX_82") (pintype "bidirectional"))
    )
    (net (code "93") (name "unconnected-(U4-PD2{slash}TIM3_ETR{slash}UART5_RXSDIO_CMD{slash}DCMI_D11-Pad83)") (class "Default")
      (node (ref "U4") (pin "83") (pinfunction "PD2/TIM3_ETR/UART5_RXSDIO_CMD/DCMI_D11_83") (pintype "bidirectional"))
    )
    (net (code "94") (name "unconnected-(U4-PD3{slash}FSMC_CLK{slash}USART2_CTS-Pad84)") (class "Default")
      (node (ref "U4") (pin "84") (pinfunction "PD3/FSMC_CLK/USART2_CTS_84") (pintype "bidirectional"))
    )
    (net (code "95") (name "unconnected-(U4-PD7{slash}USART2_CK{slash}FSMC_NE1{slash}FSMC_NCE2-Pad88)") (class "Default")
      (node (ref "U4") (pin "88") (pinfunction "PD7/USART2_CK/FSMC_NE1/FSMC_NCE2_88") (pintype "bidirectional"))
    )
    (net (code "96") (name "unconnected-(U4-PD8{slash}FSMC_D13{slash}USART3_TX-Pad55)") (class "Default")
      (node (ref "U4") (pin "55") (pinfunction "PD8/FSMC_D13/USART3_TX_55") (pintype "bidirectional"))
    )
    (net (code "97") (name "unconnected-(U4-PD9{slash}FSMC_D14{slash}USART3_RX-Pad56)") (class "Default")
      (node (ref "U4") (pin "56") (pinfunction "PD9/FSMC_D14/USART3_RX_56") (pintype "bidirectional"))
    )
    (net (code "98") (name "unconnected-(U4-PD10{slash}FSMC_D15{slash}USART3_CK-Pad57)") (class "Default")
      (node (ref "U4") (pin "57") (pinfunction "PD10/FSMC_D15/USART3_CK_57") (pintype "bidirectional"))
    )
    (net (code "99") (name "unconnected-(U4-PD11{slash}FSMC_A16{slash}USART3_CTS-Pad58)") (class "Default")
      (node (ref "U4") (pin "58") (pinfunction "PD11/FSMC_A16/USART3_CTS_58") (pintype "bidirectional"))
    )
    (net (code "100") (name "unconnected-(U4-PD12{slash}FSMC_A17{slash}TIM4_CH1{slash}USART3_RTS-Pad59)") (class "Default")
      (node (ref "U4") (pin "59") (pinfunction "PD12/FSMC_A17/TIM4_CH1/USART3_RTS_59") (pintype "bidirectional"))
    )
    (net (code "101") (name "unconnected-(U4-PD13{slash}FSMC_A18{slash}TIM4_CH2-Pad60)") (class "Default")
      (node (ref "U4") (pin "60") (pinfunction "PD13/FSMC_A18/TIM4_CH2_60") (pintype "bidirectional"))
    )
    (net (code "102") (name "unconnected-(U4-PD14{slash}FSMC_D0{slash}TIM4_CH3-Pad61)") (class "Default")
      (node (ref "U4") (pin "61") (pinfunction "PD14/FSMC_D0/TIM4_CH3_61") (pintype "bidirectional"))
    )
    (net (code "103") (name "unconnected-(U4-PD15{slash}FSMC_D1{slash}TIM4_CH4-Pad62)") (class "Default")
      (node (ref "U4") (pin "62") (pinfunction "PD15/FSMC_D1/TIM4_CH4_62") (pintype "bidirectional"))
    )
    (net (code "104") (name "unconnected-(U4-PE2{slash}TRACECLK{slash}FSMC_A23{slash}ETH_MII_TXD3-Pad1)") (class "Default")
      (node (ref "U4") (pin "1") (pinfunction "PE2/TRACECLK/FSMC_A23/ETH_MII_TXD3_1") (pintype "bidirectional"))
    )
    (net (code "105") (name "unconnected-(U4-PE3{slash}TRACED0{slash}FSMC_A19-Pad2)") (class "Default")
      (node (ref "U4") (pin "2") (pinfunction "PE3/TRACED0/FSMC_A19_2") (pintype "bidirectional"))
    )
    (net (code "106") (name "unconnected-(U4-PE7{slash}FSMC_D4{slash}TIM1_ETR-Pad38)") (class "Default")
      (node (ref "U4") (pin "38") (pinfunction "PE7/FSMC_D4/TIM1_ETR_38") (pintype "bidirectional"))
    )
    (net (code "107") (name "unconnected-(U4-PE8{slash}FSMC_D5{slash}TIM1_CH1N-Pad39)") (class "Default")
      (node (ref "U4") (pin "39") (pinfunction "PE8/FSMC_D5/TIM1_CH1N_39") (pintype "bidirectional"))
    )
    (net (code "108") (name "unconnected-(U4-PE10{slash}FSMC_D7{slash}TIM1_CH2N-Pad41)") (class "Default")
      (node (ref "U4") (pin "41") (pinfunction "PE10/FSMC_D7/TIM1_CH2N_41") (pintype "bidirectional"))
    )
    (net (code "109") (name "unconnected-(U4-PE11{slash}FSMC_D8{slash}TIM1_CH2-Pad42)") (class "Default")
      (node (ref "U4") (pin "42") (pinfunction "PE11/FSMC_D8/TIM1_CH2_42") (pintype "bidirectional"))
    )
    (net (code "110") (name "unconnected-(U4-PE12{slash}FSMC_D9{slash}TIM1_CH3N-Pad43)") (class "Default")
      (node (ref "U4") (pin "43") (pinfunction "PE12/FSMC_D9/TIM1_CH3N_43") (pintype "bidirectional"))
    )
    (net (code "111") (name "unconnected-(U4-PE13{slash}FSMC_D10{slash}TIM1_CH3-Pad44)") (class "Default")
      (node (ref "U4") (pin "44") (pinfunction "PE13/FSMC_D10/TIM1_CH3_44") (pintype "bidirectional"))
    )
    (net (code "112") (name "unconnected-(U4-PE14{slash}FSMC_D11{slash}TIM1_CH4-Pad45)") (class "Default")
      (node (ref "U4") (pin "45") (pinfunction "PE14/FSMC_D11/TIM1_CH4_45") (pintype "bidirectional"))
    )
    (net (code "113") (name "unconnected-(U4-PE15FSMC_D12{slash}TIM1_BKIN-Pad46)") (class "Default")
      (node (ref "U4") (pin "46") (pinfunction "PE15FSMC_D12/TIM1_BKIN_46") (pintype "bidirectional"))
    )
    (net (code "114") (name "unconnected-(X1-GND1-PadMT1)") (class "Default")
      (node (ref "X1") (pin "MT1") (pinfunction "GND1_MT1") (pintype "passive"))
    )
    (net (code "115") (name "unconnected-(X1-GND2-PadMT2)") (class "Default")
      (node (ref "X1") (pin "MT2") (pinfunction "GND2_MT2") (pintype "passive"))
    )
    (net (code "116") (name "unconnected-(X1-GND3-PadMT5)") (class "Default")
      (node (ref "X1") (pin "MT5") (pinfunction "GND3_MT5") (pintype "passive"))
    )
    (net (code "117") (name "unconnected-(X1-GND4-PadMT6)") (class "Default")
      (node (ref "X1") (pin "MT6") (pinfunction "GND4_MT6") (pintype "passive"))
    )
  )
)
